# CH572D-R0.net
KiCad netlist of a schematic drawn in Altium Designer
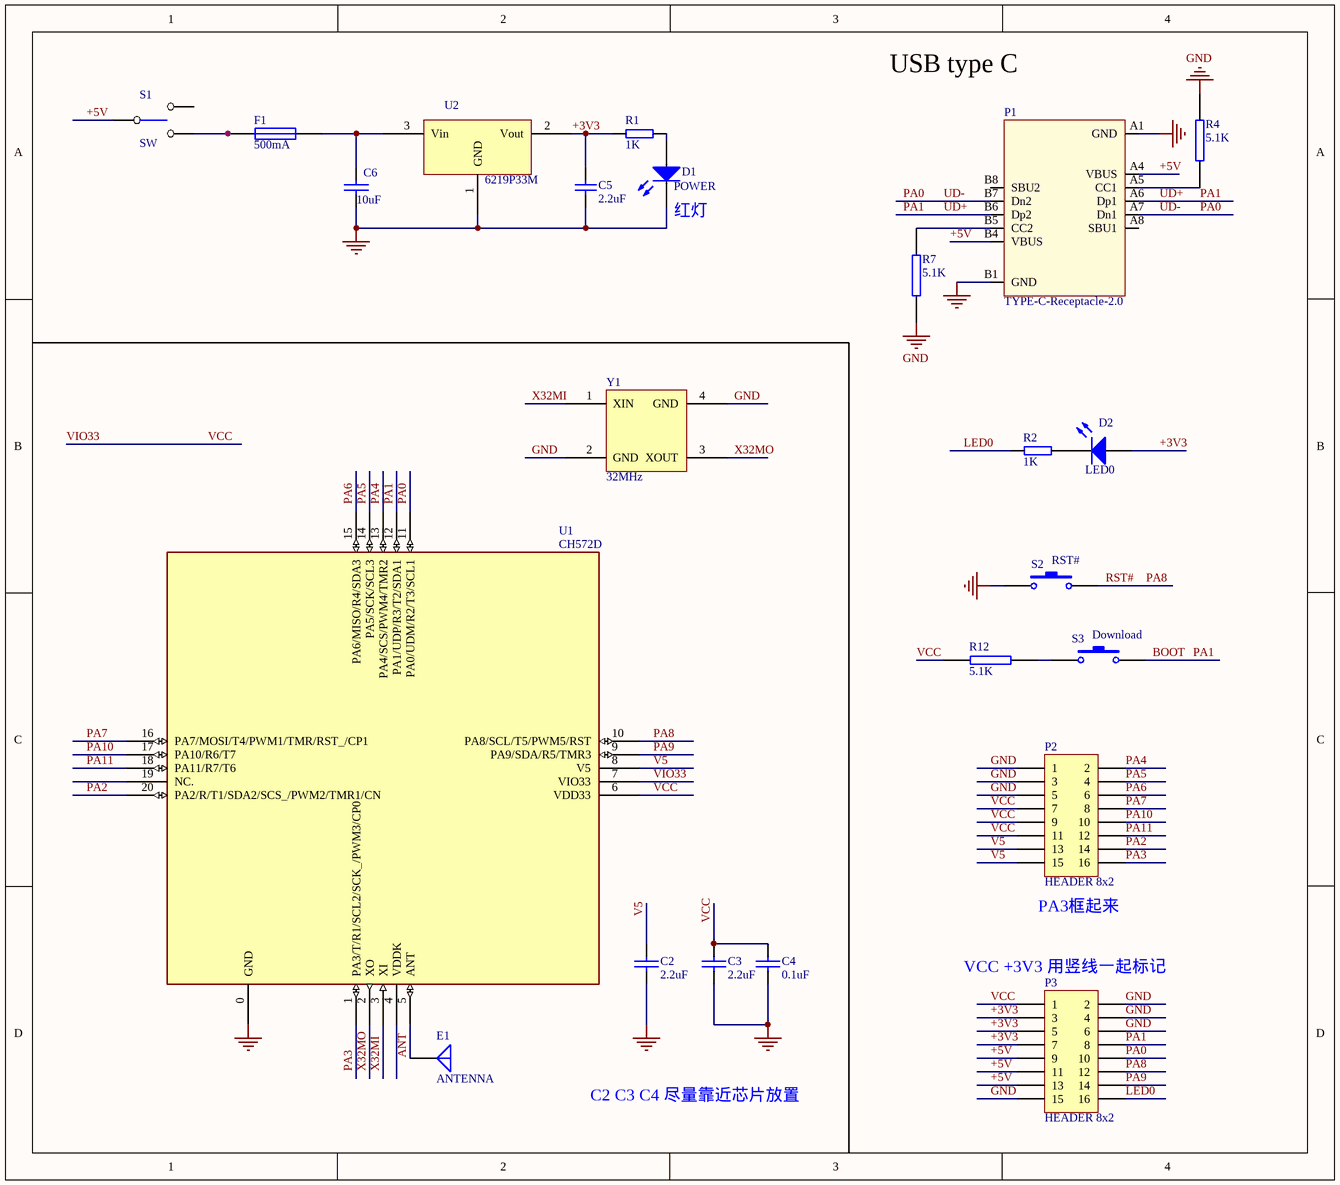
[diagram p0: CH572D-R0.SchDoc]

(export (version "E")
  (design (tool "Eeschema 10.0.6"))
  (components
    (comp (ref "C2")
      (value "2.2uF")
      (footprint "0402_C")
      (description "Capacitor")
      (libsource (lib "*") (part "CAP"))
    )
    (comp (ref "C3")
      (value "2.2uF")
      (footprint "0402_C")
      (description "Capacitor")
      (libsource (lib "*") (part "CAP"))
    )
    (comp (ref "C4")
      (value "0.1uF")
      (footprint "0402_C")
      (description "Capacitor")
      (libsource (lib "*") (part "CAP"))
    )
    (comp (ref "C5")
      (value "2.2uF")
      (footprint "0402_C")
      (description "Capacitor")
      (fields (field (name "PUBLISHER") "Altium Limited"))
      (libsource (lib "Miscellaneous Devices") (part "Cap"))
    )
    (comp (ref "C6")
      (value "10uF")
      (footprint "0603_C")
      (description "Capacitor")
      (libsource (lib "*") (part "CAP"))
    )
    (comp (ref "D1")
      (value "POWER")
      (footprint "0603+")
      (description "Typical INFRARED GaAs LED")
      (fields (field (name "PUBLISHER") "Altium Limited"))
      (libsource (lib "") (part "LED0_1"))
    )
    (comp (ref "D2")
      (value "LED0")
      (footprint "0603+")
      (description "Typical INFRARED GaAs LED")
      (fields (field (name "PUBLISHER") "Altium Limited"))
      (libsource (lib "Miscellaneous Devices") (part "LED0"))
    )
    (comp (ref "E1")
      (value "ANTENNA")
      (footprint "ANT-F-1-2.4G-1.6mmFR4")
      (description "Generic Antenna")
      (libsource (lib "*") (part "ANTENNA"))
    )
    (comp (ref "F1")
      (value "500mA")
      (footprint "0603")
      (description "Fuse")
      (libsource (lib "*") (part "FUSE1"))
    )
    (comp (ref "P1")
      (value "TYPE-C-Receptacle-2.0")
      (footprint "TYPE-C-Receptacle-2.0")
      (description "Type-C USB2.0 母座")
      (libsource (lib "Miscellaneous SCH Lib") (part "TYPE-C-Receptacle-2.0"))
    )
    (comp (ref "P2")
      (value "HEADER 8x2")
      (footprint "MYPCB:IDC16-2.54mm")
      (description "Header, 8-Pin, Dual row")
      (libsource (lib "wch_sch_others") (part "HEADER 8x2"))
    )
    (comp (ref "P3")
      (value "HEADER 8x2")
      (footprint "MYPCB:IDC16-2.54mm")
      (description "Header, 8-Pin, Dual row")
      (libsource (lib "wch_sch_others") (part "HEADER 8x2"))
    )
    (comp (ref "R1") (value "1K") (footprint "0402") (libsource (lib "wch_sch_others") (part "RES")))
    (comp (ref "R2") (value "1K") (footprint "0402") (libsource (lib "wch_sch_others") (part "RES")))
    (comp (ref "R4") (value "5.1K") (footprint "0402") (libsource (lib "*") (part "RES2")))
    (comp (ref "R7") (value "5.1K") (footprint "0402") (libsource (lib "*") (part "RES2")))
    (comp (ref "R12") (value "5.1K") (footprint "0402") (libsource (lib "*") (part "RES2")))
    (comp (ref "S1") (value "SW") (footprint "SW1") (libsource (lib "MYSCH") (part "SW")))
    (comp (ref "S2")
      (value "RST#")
      (footprint "SMD_6.1x3.65x2.5mm-KEY")
      (description "Switch")
      (fields (field (name "PUBLISHER") "Altium Limited"))
      (libsource (lib "*") (part "SW-PB"))
    )
    (comp (ref "S3")
      (value "Download")
      (footprint "SMD_6.1x3.65x2.5mm-KEY")
      (description "Switch")
      (fields (field (name "PUBLISHER") "Altium Limited"))
      (libsource (lib "*") (part "SW-PB"))
    )
    (comp (ref "U1")
      (value "CH572D")
      (footprint "QFN20_3X3")
      (description "RISC-V MCU with BLE/2.4GHz Wireless/USB/SPI/UART/I2C/PWM/CMP")
      (libsource (lib "DHXXXSCHd") (part "CH572D"))
    )
    (comp (ref "U2")
      (value "6219P33M")
      (footprint "SOT-23")
      (libsource (lib "wch_sch_others") (part "6219P33M"))
    )
    (comp (ref "Y1") (value "32MHz") (footprint "XT3225") (libsource (lib "wch_sch_others") (part "晶体")))
  )
  (nets
    (net (code "1") (name "/+3V3") (class "Default")
      (node (ref "C5") (pin "2") (pinfunction "2_2") (pintype "passive"))
      (node (ref "D2") (pin "1") (pinfunction "A_1") (pintype "passive"))
      (node (ref "P3") (pin "3") (pinfunction "3_3") (pintype "passive"))
      (node (ref "P3") (pin "5") (pinfunction "5_5") (pintype "passive"))
      (node (ref "P3") (pin "7") (pinfunction "7_7") (pintype "passive"))
      (node (ref "R1") (pin "2") (pintype "passive"))
      (node (ref "U2") (pin "2") (pinfunction "Vout_2") (pintype "passive"))
    )
    (net (code "2") (name "/+5V") (class "Default")
      (node (ref "P1") (pin "A4") (pinfunction "VBUS_A4") (pintype "passive"))
      (node (ref "P1") (pin "B4") (pinfunction "VBUS_B4") (pintype "passive"))
      (node (ref "P3") (pin "11") (pinfunction "11_11") (pintype "passive"))
      (node (ref "P3") (pin "13") (pinfunction "13_13") (pintype "passive"))
      (node (ref "P3") (pin "9") (pinfunction "9_9") (pintype "passive"))
      (node (ref "S1") (pin "1") (pinfunction "1_1") (pintype "passive"))
    )
    (net (code "3") (name "/ANT") (class "Default")
      (node (ref "E1") (pin "1") (pinfunction "A_1") (pintype "passive"))
      (node (ref "U1") (pin "5") (pinfunction "ANT_5") (pintype "bidirectional"))
    )
    (net (code "4") (name "/BOOT") (class "Default")
      (node (ref "P1") (pin "A6") (pinfunction "Dp1_A6") (pintype "passive"))
      (node (ref "P1") (pin "B6") (pinfunction "Dp2_B6") (pintype "passive"))
      (node (ref "P3") (pin "8") (pinfunction "8_8") (pintype "passive"))
      (node (ref "S3") (pin "2") (pinfunction "2_2") (pintype "passive"))
      (node (ref "U1") (pin "12") (pinfunction "PA1/UDP/R3/T2/SDA1_12") (pintype "bidirectional"))
    )
    (net (code "5") (name "/LED0") (class "Default")
      (node (ref "P3") (pin "16") (pinfunction "16_16") (pintype "passive"))
      (node (ref "R2") (pin "1") (pintype "passive"))
    )
    (net (code "6") (name "/PA0") (class "Default")
      (node (ref "P1") (pin "A7") (pinfunction "Dn1_A7") (pintype "passive"))
      (node (ref "P1") (pin "B7") (pinfunction "Dn2_B7") (pintype "passive"))
      (node (ref "P3") (pin "10") (pinfunction "10_10") (pintype "passive"))
      (node (ref "U1") (pin "11") (pinfunction "PA0/UDM/R2/T3/SCL1_11") (pintype "bidirectional"))
    )
    (net (code "7") (name "/PA2") (class "Default")
      (node (ref "P2") (pin "14") (pinfunction "14_14") (pintype "passive"))
      (node (ref "U1") (pin "20") (pinfunction "PA2/R/T1/SDA2/SCS_/PWM2/TMR1/CN_20") (pintype "bidirectional"))
    )
    (net (code "8") (name "/PA3") (class "Default")
      (node (ref "P2") (pin "16") (pinfunction "16_16") (pintype "passive"))
      (node (ref "U1") (pin "1") (pinfunction "PA3/T/R1/SCL2/SCK_/PWM3/CP0_1") (pintype "bidirectional"))
    )
    (net (code "9") (name "/PA4") (class "Default")
      (node (ref "P2") (pin "2") (pinfunction "2_2") (pintype "passive"))
      (node (ref "U1") (pin "13") (pinfunction "PA4/SCS/PWM4/TMR2_13") (pintype "bidirectional"))
    )
    (net (code "10") (name "/PA5") (class "Default")
      (node (ref "P2") (pin "4") (pinfunction "4_4") (pintype "passive"))
      (node (ref "U1") (pin "14") (pinfunction "PA5/SCK/SCL3_14") (pintype "bidirectional"))
    )
    (net (code "11") (name "/PA6") (class "Default")
      (node (ref "P2") (pin "6") (pinfunction "6_6") (pintype "passive"))
      (node (ref "U1") (pin "15") (pinfunction "PA6/MISO/R4/SDA3_15") (pintype "bidirectional"))
    )
    (net (code "12") (name "/PA7") (class "Default")
      (node (ref "P2") (pin "8") (pinfunction "8_8") (pintype "passive"))
      (node (ref "U1") (pin "16") (pinfunction "PA7/MOSI/T4/PWM1/TMR/RST_/CP1_16") (pintype "bidirectional"))
    )
    (net (code "13") (name "/PA8") (class "Default")
      (node (ref "P3") (pin "12") (pinfunction "12_12") (pintype "passive"))
      (node (ref "S2") (pin "2") (pinfunction "2_2") (pintype "passive"))
      (node (ref "U1") (pin "10") (pinfunction "PA8/SCL/T5/PWM5/RST_10") (pintype "bidirectional"))
    )
    (net (code "14") (name "/PA9") (class "Default")
      (node (ref "P3") (pin "14") (pinfunction "14_14") (pintype "passive"))
      (node (ref "U1") (pin "9") (pinfunction "PA9/SDA/R5/TMR3_9") (pintype "bidirectional"))
    )
    (net (code "15") (name "/PA10") (class "Default")
      (node (ref "P2") (pin "10") (pinfunction "10_10") (pintype "passive"))
      (node (ref "U1") (pin "17") (pinfunction "PA10/R6/T7_17") (pintype "bidirectional"))
    )
    (net (code "16") (name "/PA11") (class "Default")
      (node (ref "P2") (pin "12") (pinfunction "12_12") (pintype "passive"))
      (node (ref "U1") (pin "18") (pinfunction "PA11/R7/T6_18") (pintype "bidirectional"))
    )
    (net (code "17") (name "/V5") (class "Default")
      (node (ref "C2") (pin "1") (pinfunction "1_1") (pintype "passive"))
      (node (ref "P2") (pin "13") (pinfunction "13_13") (pintype "passive"))
      (node (ref "P2") (pin "15") (pinfunction "15_15") (pintype "passive"))
      (node (ref "U1") (pin "8") (pinfunction "V5_8") (pintype "power_in"))
    )
    (net (code "18") (name "/VCC") (class "Default")
      (node (ref "C3") (pin "1") (pinfunction "1_1") (pintype "passive"))
      (node (ref "C4") (pin "1") (pinfunction "1_1") (pintype "passive"))
      (node (ref "P2") (pin "11") (pinfunction "11_11") (pintype "passive"))
      (node (ref "P2") (pin "7") (pinfunction "7_7") (pintype "passive"))
      (node (ref "P2") (pin "9") (pinfunction "9_9") (pintype "passive"))
      (node (ref "P3") (pin "1") (pinfunction "1_1") (pintype "passive"))
      (node (ref "R12") (pin "2") (pinfunction "2_2") (pintype "passive"))
      (node (ref "U1") (pin "6") (pinfunction "VDD33_6") (pintype "power_in"))
      (node (ref "U1") (pin "7") (pinfunction "VIO33_7") (pintype "power_in"))
    )
    (net (code "19") (name "/X32MI") (class "Default")
      (node (ref "U1") (pin "3") (pinfunction "XI_3") (pintype "input"))
      (node (ref "Y1") (pin "1") (pinfunction "XIN_1") (pintype "passive"))
    )
    (net (code "20") (name "/X32MO") (class "Default")
      (node (ref "U1") (pin "2") (pinfunction "XO_2") (pintype "output"))
      (node (ref "Y1") (pin "3") (pinfunction "XOUT_3") (pintype "passive"))
    )
    (net (code "21") (name "GND") (class "Default")
      (node (ref "C2") (pin "2") (pinfunction "2_2") (pintype "passive"))
      (node (ref "C3") (pin "2") (pinfunction "2_2") (pintype "passive"))
      (node (ref "C4") (pin "2") (pinfunction "2_2") (pintype "passive"))
      (node (ref "C5") (pin "1") (pinfunction "1_1") (pintype "passive"))
      (node (ref "C6") (pin "2") (pinfunction "2_2") (pintype "passive"))
      (node (ref "D1") (pin "2") (pinfunction "K_2") (pintype "passive"))
      (node (ref "P1") (pin "A1") (pinfunction "GND_A1") (pintype "passive"))
      (node (ref "P1") (pin "B1") (pinfunction "GND_B1") (pintype "passive"))
      (node (ref "P2") (pin "1") (pinfunction "1_1") (pintype "passive"))
      (node (ref "P2") (pin "3") (pinfunction "3_3") (pintype "passive"))
      (node (ref "P2") (pin "5") (pinfunction "5_5") (pintype "passive"))
      (node (ref "P3") (pin "15") (pinfunction "15_15") (pintype "passive"))
      (node (ref "P3") (pin "2") (pinfunction "2_2") (pintype "passive"))
      (node (ref "P3") (pin "4") (pinfunction "4_4") (pintype "passive"))
      (node (ref "P3") (pin "6") (pinfunction "6_6") (pintype "passive"))
      (node (ref "R4") (pin "2") (pinfunction "2_2") (pintype "passive"))
      (node (ref "R7") (pin "1") (pinfunction "1_1") (pintype "passive"))
      (node (ref "S2") (pin "1") (pinfunction "1_1") (pintype "passive"))
      (node (ref "U1") (pin "0") (pinfunction "GND_0") (pintype "power_in"))
      (node (ref "U2") (pin "1") (pinfunction "GND_1") (pintype "passive"))
      (node (ref "Y1") (pin "2") (pinfunction "GND_2") (pintype "passive"))
      (node (ref "Y1") (pin "4") (pinfunction "GND_4") (pintype "passive"))
    )
    (net (code "22") (name "Net-(D1-A)") (class "Default")
      (node (ref "D1") (pin "1") (pinfunction "A_1") (pintype "passive"))
      (node (ref "R1") (pin "1") (pintype "passive"))
    )
    (net (code "23") (name "Net-(D2-K)") (class "Default")
      (node (ref "D2") (pin "2") (pinfunction "K_2") (pintype "passive"))
      (node (ref "R2") (pin "2") (pintype "passive"))
    )
    (net (code "24") (name "Net-(F1-Pad1)") (class "Default")
      (node (ref "F1") (pin "1") (pinfunction "1_1") (pintype "passive"))
      (node (ref "S1") (pin "2") (pinfunction "2_2") (pintype "passive"))
    )
    (net (code "25") (name "Net-(P1-CC1)") (class "Default")
      (node (ref "P1") (pin "A5") (pinfunction "CC1_A5") (pintype "passive"))
      (node (ref "R4") (pin "1") (pinfunction "1_1") (pintype "passive"))
    )
    (net (code "26") (name "Net-(P1-CC2)") (class "Default")
      (node (ref "P1") (pin "B5") (pinfunction "CC2_B5") (pintype "passive"))
      (node (ref "R7") (pin "2") (pinfunction "2_2") (pintype "passive"))
    )
    (net (code "27") (name "Net-(R12-Pad1)") (class "Default")
      (node (ref "R12") (pin "1") (pinfunction "1_1") (pintype "passive"))
      (node (ref "S3") (pin "1") (pinfunction "1_1") (pintype "passive"))
    )
    (net (code "28") (name "Net-(U2-Vin)") (class "Default")
      (node (ref "C6") (pin "1") (pinfunction "1_1") (pintype "passive"))
      (node (ref "F1") (pin "2") (pinfunction "2_2") (pintype "passive"))
      (node (ref "U2") (pin "3") (pinfunction "Vin_3") (pintype "passive"))
    )
    (net (code "29") (name "unconnected-(P1-SBU1-PadA8)") (class "Default")
      (node (ref "P1") (pin "A8") (pinfunction "SBU1_A8") (pintype "passive"))
    )
    (net (code "30") (name "unconnected-(P1-SBU2-PadB8)") (class "Default")
      (node (ref "P1") (pin "B8") (pinfunction "SBU2_B8") (pintype "passive"))
    )
    (net (code "31") (name "unconnected-(S1-Pad3)") (class "Default")
      (node (ref "S1") (pin "3") (pinfunction "3_3") (pintype "passive"))
    )
    (net (code "32") (name "unconnected-(U1-NC.-Pad19)") (class "Default")
      (node (ref "U1") (pin "19") (pinfunction "NC._19") (pintype "passive"))
    )
    (net (code "33") (name "unconnected-(U1-VDDK-Pad4)") (class "Default")
      (node (ref "U1") (pin "4") (pinfunction "VDDK_4") (pintype "power_in"))
    )
  )
)
